# 16gpio_misc.net
KiCad netlist of a schematic drawn in Altium Designer
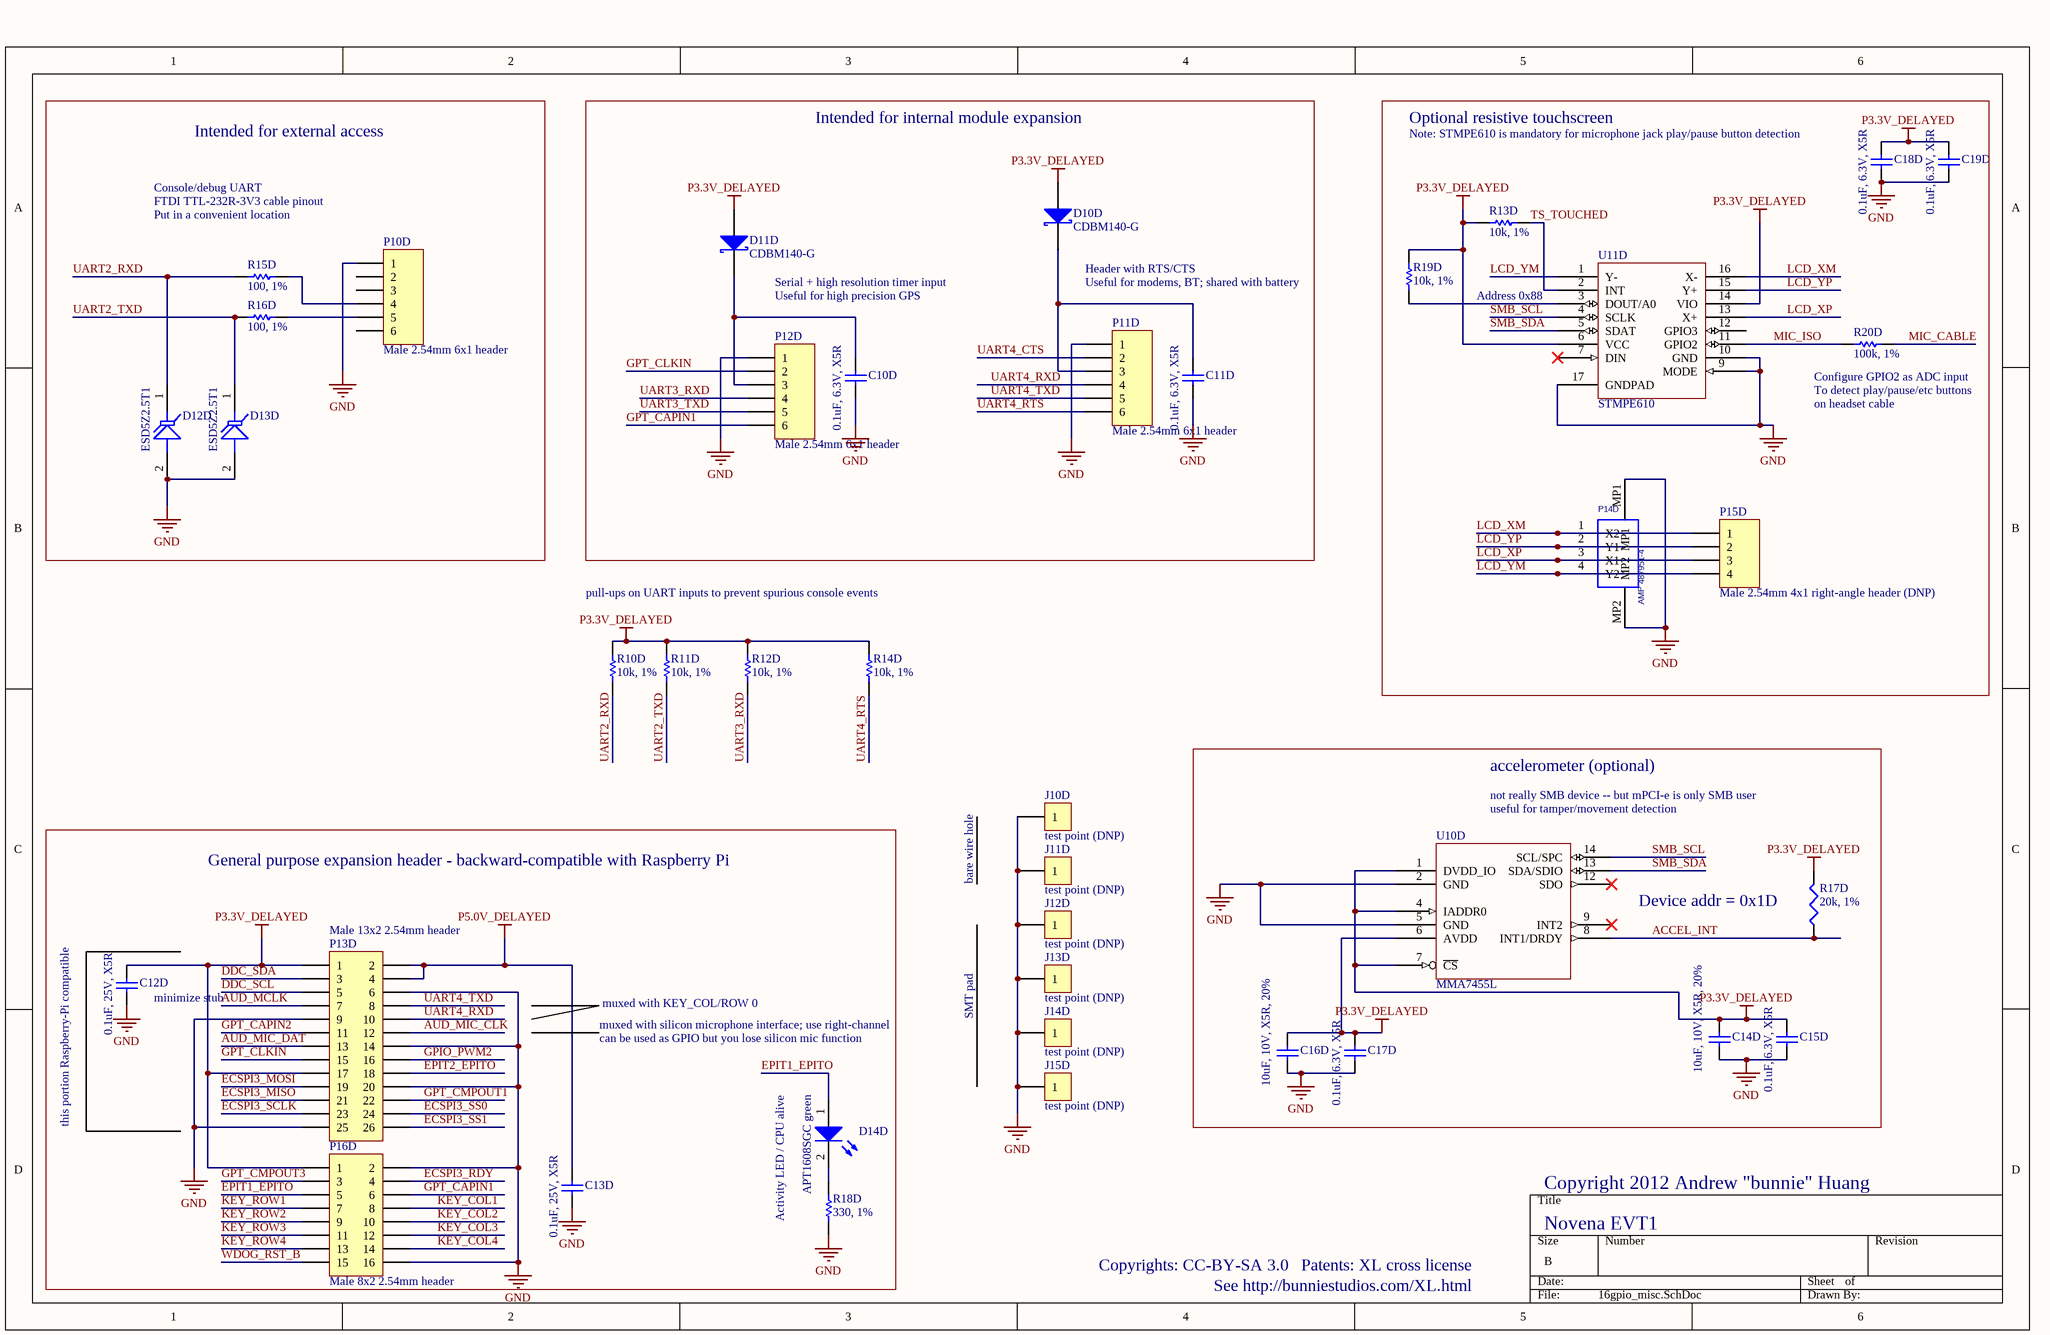
[diagram p0: 16gpio_misc.SchDoc]

(export (version "E")
  (design (tool "Eeschema 10.0.6"))
  (components
    (comp (ref "C10D")
      (value "0.1uF, 6.3V, X5R")
      (footprint "CAPC0603N_B")
      (description "Capacitor (Semiconductor SIM Model)")
      (fields (field (name "PUBLISHER") "Altium Limited"))
      (libsource (lib "Miscellaneous Devices") (part "Cap Semi"))
    )
    (comp (ref "C11D")
      (value "0.1uF, 6.3V, X5R")
      (footprint "CAPC0603N_B")
      (description "Capacitor (Semiconductor SIM Model)")
      (fields (field (name "PUBLISHER") "Altium Limited"))
      (libsource (lib "Miscellaneous Devices") (part "Cap Semi"))
    )
    (comp (ref "C12D")
      (value "0.1uF, 25V, X5R")
      (footprint "CAPC1005N")
      (description "Capacitor (Semiconductor SIM Model)")
      (fields (field (name "PUBLISHER") "Altium Limited"))
      (libsource (lib "Miscellaneous Devices") (part "Cap Semi"))
    )
    (comp (ref "C13D")
      (value "0.1uF, 25V, X5R")
      (footprint "CAPC1005N")
      (description "Capacitor (Semiconductor SIM Model)")
      (fields (field (name "PUBLISHER") "Altium Limited"))
      (libsource (lib "Miscellaneous Devices") (part "Cap Semi"))
    )
    (comp (ref "C14D")
      (value "10uF, 10V, X5R, 20%")
      (footprint "CAPC1608N")
      (description "Capacitor (Semiconductor SIM Model)")
      (fields (field (name "PUBLISHER") "Altium Limited"))
      (libsource (lib "Miscellaneous Devices") (part "Cap Semi"))
    )
    (comp (ref "C15D")
      (value "0.1uF, 6.3V, X5R")
      (footprint "CAPC0603N_B")
      (description "Capacitor (Semiconductor SIM Model)")
      (fields (field (name "PUBLISHER") "Altium Limited"))
      (libsource (lib "Miscellaneous Devices") (part "Cap Semi"))
    )
    (comp (ref "C16D")
      (value "10uF, 10V, X5R, 20%")
      (footprint "CAPC1608N")
      (description "Capacitor (Semiconductor SIM Model)")
      (fields (field (name "PUBLISHER") "Altium Limited"))
      (libsource (lib "Miscellaneous Devices") (part "Cap Semi"))
    )
    (comp (ref "C17D")
      (value "0.1uF, 6.3V, X5R")
      (footprint "CAPC0603N_B")
      (description "Capacitor (Semiconductor SIM Model)")
      (fields (field (name "PUBLISHER") "Altium Limited"))
      (libsource (lib "Miscellaneous Devices") (part "Cap Semi"))
    )
    (comp (ref "C18D")
      (value "0.1uF, 6.3V, X5R")
      (footprint "CAPC0603N_B")
      (description "Capacitor (Semiconductor SIM Model)")
      (fields (field (name "PUBLISHER") "Altium Limited"))
      (libsource (lib "Miscellaneous Devices") (part "Cap Semi"))
    )
    (comp (ref "C19D")
      (value "0.1uF, 6.3V, X5R")
      (footprint "CAPC0603N_B")
      (description "Capacitor (Semiconductor SIM Model)")
      (fields (field (name "PUBLISHER") "Altium Limited"))
      (libsource (lib "Miscellaneous Devices") (part "Cap Semi"))
    )
    (comp (ref "D10D")
      (value "CDBM140-G")
      (footprint "SOD123")
      (description "Schottky Diode")
      (fields (field (name "PUBLISHER") "Altium Limited"))
      (libsource (lib "Miscellaneous Devices") (part "D Schottky"))
    )
    (comp (ref "D11D")
      (value "CDBM140-G")
      (footprint "SOD123")
      (description "Schottky Diode")
      (fields (field (name "PUBLISHER") "Altium Limited"))
      (libsource (lib "Miscellaneous Devices") (part "D Schottky"))
    )
    (comp (ref "D12D")
      (value "ESD5Z2.5T1")
      (footprint "SOD-523")
      (description "On Semi 3.3V standoff TVS diode")
      (fields (field (name "PUBLISHER") "Altium Limited"))
      (libsource (lib "Miscellaneous Devices") (part "Tranzorb"))
    )
    (comp (ref "D13D")
      (value "ESD5Z2.5T1")
      (footprint "SOD-523")
      (description "On Semi 3.3V standoff TVS diode")
      (fields (field (name "PUBLISHER") "Altium Limited"))
      (libsource (lib "Miscellaneous Devices") (part "Tranzorb"))
    )
    (comp (ref "D14D")
      (value "APT1608SGC green")
      (footprint "CD1608-0603")
      (description "Typical RED, GREEN, YELLOW, AMBER GaAs LED")
      (fields (field (name "PUBLISHER") "Altium Limited"))
      (libsource (lib "Miscellaneous Devices") (part "LED2"))
    )
    (comp (ref "J10D")
      (value "test point (DNP)")
      (footprint "TP_HOLE")
      (description "Connector")
      (libsource (lib "*") (part "CON1"))
    )
    (comp (ref "J11D")
      (value "test point (DNP)")
      (footprint "TP_HOLE")
      (description "Connector")
      (libsource (lib "*") (part "CON1"))
    )
    (comp (ref "J12D")
      (value "test point (DNP)")
      (footprint "TP_SMT_38mil")
      (description "Connector")
      (libsource (lib "*") (part "CON1"))
    )
    (comp (ref "J13D")
      (value "test point (DNP)")
      (footprint "TP_SMT_38mil")
      (description "Connector")
      (libsource (lib "*") (part "CON1"))
    )
    (comp (ref "J14D")
      (value "test point (DNP)")
      (footprint "TP_SMT_38mil")
      (description "Connector")
      (libsource (lib "*") (part "CON1"))
    )
    (comp (ref "J15D")
      (value "test point (DNP)")
      (footprint "TP_SMT_38mil")
      (description "Connector")
      (libsource (lib "*") (part "CON1"))
    )
    (comp (ref "P10D")
      (value "Male 2.54mm 6x1 header")
      (footprint "HDR1X6")
      (description "Header, 6-Pin")
      (fields (field (name "PUBLISHER") "Altium Limited"))
      (libsource (lib "Miscellaneous Connectors") (part "Header 6"))
    )
    (comp (ref "P11D")
      (value "Male 2.54mm 6x1 header")
      (footprint "HDR1X6")
      (description "Header, 6-Pin")
      (fields (field (name "PUBLISHER") "Altium Limited"))
      (libsource (lib "Miscellaneous Connectors") (part "Header 6"))
    )
    (comp (ref "P12D")
      (value "Male 2.54mm 6x1 header")
      (footprint "HDR1X6")
      (description "Header, 6-Pin")
      (fields (field (name "PUBLISHER") "Altium Limited"))
      (libsource (lib "Miscellaneous Connectors") (part "Header 6"))
    )
    (comp (ref "P13D")
      (value "Male 13x2 2.54mm header")
      (footprint "HDR2X13")
      (description "Header, 13-Pin, Dual row")
      (fields (field (name "PUBLISHER") "Altium Limited"))
      (libsource (lib "Miscellaneous Connectors") (part "Header 13X2"))
    )
    (comp (ref "P14D") (value "AMP 487951-4") (libsource (lib "*") (part "TFT_TP_CON")))
    (comp (ref "P15D")
      (value "Male 2.54mm 4x1 right-angle header (DNP)")
      (footprint "HDR1X4H")
      (description "Header, 4-Pin, Right Angle")
      (fields (field (name "PUBLISHER") "Altium Limited"))
      (libsource (lib "Miscellaneous Connectors") (part "Header 4H"))
    )
    (comp (ref "P16D")
      (value "Male 8x2 2.54mm header")
      (footprint "HDR2X8")
      (description "Header, 8-Pin, Dual row")
      (fields (field (name "PUBLISHER") "Altium Limited"))
      (libsource (lib "Miscellaneous Connectors") (part "Header 8X2"))
    )
    (comp (ref "R10D")
      (value "10k, 1%")
      (footprint "RESC1005N")
      (description "Resistor")
      (fields (field (name "PUBLISHER") "Altium Limited"))
      (libsource (lib "Miscellaneous Devices") (part "Res1"))
    )
    (comp (ref "R11D")
      (value "10k, 1%")
      (footprint "RESC1005N")
      (description "Resistor")
      (fields (field (name "PUBLISHER") "Altium Limited"))
      (libsource (lib "Miscellaneous Devices") (part "Res1"))
    )
    (comp (ref "R12D")
      (value "10k, 1%")
      (footprint "RESC1005N")
      (description "Resistor")
      (fields (field (name "PUBLISHER") "Altium Limited"))
      (libsource (lib "Miscellaneous Devices") (part "Res1"))
    )
    (comp (ref "R13D")
      (value "10k, 1%")
      (footprint "RESC1005N")
      (description "Resistor")
      (fields (field (name "PUBLISHER") "Altium Limited"))
      (libsource (lib "Miscellaneous Devices") (part "Res1"))
    )
    (comp (ref "R14D")
      (value "10k, 1%")
      (footprint "RESC1005N")
      (description "Resistor")
      (fields (field (name "PUBLISHER") "Altium Limited"))
      (libsource (lib "Miscellaneous Devices") (part "Res1"))
    )
    (comp (ref "R15D")
      (value "100, 1%")
      (footprint "RESC1005N")
      (description "Resistor")
      (fields (field (name "PUBLISHER") "Altium Limited"))
      (libsource (lib "Miscellaneous Devices") (part "Res1"))
    )
    (comp (ref "R16D")
      (value "100, 1%")
      (footprint "RESC1005N")
      (description "Resistor")
      (fields (field (name "PUBLISHER") "Altium Limited"))
      (libsource (lib "Miscellaneous Devices") (part "Res1"))
    )
    (comp (ref "R17D")
      (value "20k, 1%")
      (footprint "RESC1005N")
      (description "Resistor")
      (fields (field (name "PUBLISHER") "Altium Limited"))
      (libsource (lib "Miscellaneous Devices") (part "Res3"))
    )
    (comp (ref "R18D")
      (value "330, 1%")
      (footprint "RESC1005N")
      (description "Resistor")
      (fields (field (name "PUBLISHER") "Altium Limited"))
      (libsource (lib "Miscellaneous Devices") (part "Res1"))
    )
    (comp (ref "R19D")
      (value "10k, 1%")
      (footprint "RESC1005N")
      (description "Resistor")
      (fields (field (name "PUBLISHER") "Altium Limited"))
      (libsource (lib "Miscellaneous Devices") (part "Res1"))
    )
    (comp (ref "R20D")
      (value "100k, 1%")
      (footprint "RESC1005N")
      (description "Resistor")
      (fields (field (name "PUBLISHER") "Altium Limited"))
      (libsource (lib "Miscellaneous Devices") (part "Res1"))
    )
    (comp (ref "U10D")
      (value "MMA7455L")
      (footprint "FREESCALE_LGA14_3mm_5mm")
      (description "3-axis accelerometer, 10 bit, selectable g-range")
      (libsource (lib "commonsch") (part "FREESCALE_MMA7455L"))
    )
    (comp (ref "U11D")
      (value "STMPE610")
      (footprint "QFN50P300X300-16V2N")
      (description "4-wire resistive touchscreen controller")
      (libsource (lib "commonsch") (part "STMPE610"))
    )
  )
  (nets
    (net (code "1") (name "/ACCEL_INT") (class "Default")
      (node (ref "R17D") (pin "1") (pinfunction "1_1") (pintype "passive"))
      (node (ref "U10D") (pin "8") (pinfunction "INT1/DRDY_8") (pintype "output"))
    )
    (net (code "2") (name "/AUD_MCLK") (class "Default")
      (node (ref "P13D") (pin "7") (pinfunction "7_7") (pintype "passive"))
    )
    (net (code "3") (name "/AUD_MIC_CLK") (class "Default")
      (node (ref "P13D") (pin "12") (pinfunction "12_12") (pintype "passive"))
    )
    (net (code "4") (name "/AUD_MIC_DAT") (class "Default")
      (node (ref "P13D") (pin "13") (pinfunction "13_13") (pintype "passive"))
    )
    (net (code "5") (name "/DDC_SCL") (class "Default")
      (node (ref "P13D") (pin "5") (pinfunction "5_5") (pintype "passive"))
    )
    (net (code "6") (name "/DDC_SDA") (class "Default")
      (node (ref "P13D") (pin "3") (pinfunction "3_3") (pintype "passive"))
    )
    (net (code "7") (name "/ECSPI3_MISO") (class "Default")
      (node (ref "P13D") (pin "21") (pinfunction "21_21") (pintype "passive"))
    )
    (net (code "8") (name "/ECSPI3_MOSI") (class "Default")
      (node (ref "P13D") (pin "19") (pinfunction "19_19") (pintype "passive"))
    )
    (net (code "9") (name "/ECSPI3_RDY") (class "Default")
      (node (ref "P16D") (pin "4") (pinfunction "4_4") (pintype "passive"))
    )
    (net (code "10") (name "/ECSPI3_SCLK") (class "Default")
      (node (ref "P13D") (pin "23") (pinfunction "23_23") (pintype "passive"))
    )
    (net (code "11") (name "/ECSPI3_SS0") (class "Default")
      (node (ref "P13D") (pin "24") (pinfunction "24_24") (pintype "passive"))
    )
    (net (code "12") (name "/ECSPI3_SS1") (class "Default")
      (node (ref "P13D") (pin "26") (pinfunction "26_26") (pintype "passive"))
    )
    (net (code "13") (name "/EPIT1_EPITO") (class "Default")
      (node (ref "D14D") (pin "1") (pinfunction "A_1") (pintype "passive"))
      (node (ref "P16D") (pin "5") (pinfunction "5_5") (pintype "passive"))
    )
    (net (code "14") (name "/EPIT2_EPITO") (class "Default")
      (node (ref "P13D") (pin "18") (pinfunction "18_18") (pintype "passive"))
    )
    (net (code "15") (name "/GPIO_PWM2") (class "Default")
      (node (ref "P13D") (pin "16") (pinfunction "16_16") (pintype "passive"))
    )
    (net (code "16") (name "/GPT_CAPIN1") (class "Default")
      (node (ref "P12D") (pin "6") (pinfunction "6_6") (pintype "passive"))
      (node (ref "P16D") (pin "6") (pinfunction "6_6") (pintype "passive"))
    )
    (net (code "17") (name "/GPT_CAPIN2") (class "Default")
      (node (ref "P13D") (pin "11") (pinfunction "11_11") (pintype "passive"))
    )
    (net (code "18") (name "/GPT_CLKIN") (class "Default")
      (node (ref "P12D") (pin "2") (pinfunction "2_2") (pintype "passive"))
      (node (ref "P13D") (pin "15") (pinfunction "15_15") (pintype "passive"))
    )
    (net (code "19") (name "/GPT_CMPOUT1") (class "Default")
      (node (ref "P13D") (pin "22") (pinfunction "22_22") (pintype "passive"))
    )
    (net (code "20") (name "/GPT_CMPOUT3") (class "Default")
      (node (ref "P16D") (pin "3") (pinfunction "3_3") (pintype "passive"))
    )
    (net (code "21") (name "/KEY_COL1") (class "Default")
      (node (ref "P16D") (pin "8") (pinfunction "8_8") (pintype "passive"))
    )
    (net (code "22") (name "/KEY_COL2") (class "Default")
      (node (ref "P16D") (pin "10") (pinfunction "10_10") (pintype "passive"))
    )
    (net (code "23") (name "/KEY_COL3") (class "Default")
      (node (ref "P16D") (pin "12") (pinfunction "12_12") (pintype "passive"))
    )
    (net (code "24") (name "/KEY_COL4") (class "Default")
      (node (ref "P16D") (pin "14") (pinfunction "14_14") (pintype "passive"))
    )
    (net (code "25") (name "/KEY_ROW1") (class "Default")
      (node (ref "P16D") (pin "7") (pinfunction "7_7") (pintype "passive"))
    )
    (net (code "26") (name "/KEY_ROW2") (class "Default")
      (node (ref "P16D") (pin "9") (pinfunction "9_9") (pintype "passive"))
    )
    (net (code "27") (name "/KEY_ROW3") (class "Default")
      (node (ref "P16D") (pin "11") (pinfunction "11_11") (pintype "passive"))
    )
    (net (code "28") (name "/KEY_ROW4") (class "Default")
      (node (ref "P16D") (pin "13") (pinfunction "13_13") (pintype "passive"))
    )
    (net (code "29") (name "/LCD_XM") (class "Default")
      (node (ref "P14D") (pin "1") (pinfunction "X2_1") (pintype "passive"))
      (node (ref "P15D") (pin "1") (pinfunction "1_1") (pintype "passive"))
      (node (ref "U11D") (pin "16") (pinfunction "X-_16") (pintype "passive"))
    )
    (net (code "30") (name "/LCD_XP") (class "Default")
      (node (ref "P14D") (pin "3") (pinfunction "X1_3") (pintype "passive"))
      (node (ref "P15D") (pin "3") (pinfunction "3_3") (pintype "passive"))
      (node (ref "U11D") (pin "13") (pinfunction "X+_13") (pintype "passive"))
    )
    (net (code "31") (name "/LCD_YM") (class "Default")
      (node (ref "P14D") (pin "4") (pinfunction "Y2_4") (pintype "passive"))
      (node (ref "P15D") (pin "4") (pinfunction "4_4") (pintype "passive"))
      (node (ref "U11D") (pin "1") (pinfunction "Y-_1") (pintype "passive"))
    )
    (net (code "32") (name "/LCD_YP") (class "Default")
      (node (ref "P14D") (pin "2") (pinfunction "Y1_2") (pintype "passive"))
      (node (ref "P15D") (pin "2") (pinfunction "2_2") (pintype "passive"))
      (node (ref "U11D") (pin "15") (pinfunction "Y+_15") (pintype "passive"))
    )
    (net (code "33") (name "/MIC_CABLE") (class "Default")
      (node (ref "R20D") (pin "2") (pinfunction "2_2") (pintype "passive"))
    )
    (net (code "34") (name "/MIC_ISO") (class "Default")
      (node (ref "R20D") (pin "1") (pinfunction "1_1") (pintype "passive"))
      (node (ref "U11D") (pin "11") (pinfunction "GPIO2_11") (pintype "bidirectional"))
    )
    (net (code "35") (name "/SMB_SCL") (class "Default")
      (node (ref "U10D") (pin "14") (pinfunction "SCL/SPC_14") (pintype "bidirectional"))
      (node (ref "U11D") (pin "4") (pinfunction "SCLK_4") (pintype "bidirectional"))
    )
    (net (code "36") (name "/SMB_SDA") (class "Default")
      (node (ref "U10D") (pin "13") (pinfunction "SDA/SDIO_13") (pintype "bidirectional"))
      (node (ref "U11D") (pin "5") (pinfunction "SDAT_5") (pintype "bidirectional"))
    )
    (net (code "37") (name "/TS_TOUCHED") (class "Default")
      (node (ref "R13D") (pin "1") (pinfunction "1_1") (pintype "passive"))
      (node (ref "U11D") (pin "2") (pinfunction "INT_2") (pintype "open_collector"))
    )
    (net (code "38") (name "/UART2_RXD") (class "Default")
      (node (ref "D12D") (pin "1") (pinfunction "K_1") (pintype "passive"))
      (node (ref "R10D") (pin "2") (pinfunction "2_2") (pintype "passive"))
      (node (ref "R15D") (pin "2") (pinfunction "2_2") (pintype "passive"))
    )
    (net (code "39") (name "/UART2_TXD") (class "Default")
      (node (ref "D13D") (pin "1") (pinfunction "K_1") (pintype "passive"))
      (node (ref "R11D") (pin "2") (pinfunction "2_2") (pintype "passive"))
      (node (ref "R16D") (pin "2") (pinfunction "2_2") (pintype "passive"))
    )
    (net (code "40") (name "/UART3_RXD") (class "Default")
      (node (ref "P12D") (pin "4") (pinfunction "4_4") (pintype "passive"))
      (node (ref "R12D") (pin "2") (pinfunction "2_2") (pintype "passive"))
    )
    (net (code "41") (name "/UART3_TXD") (class "Default")
      (node (ref "P12D") (pin "5") (pinfunction "5_5") (pintype "passive"))
    )
    (net (code "42") (name "/UART4_CTS") (class "Default")
      (node (ref "P11D") (pin "2") (pinfunction "2_2") (pintype "passive"))
    )
    (net (code "43") (name "/UART4_RTS") (class "Default")
      (node (ref "P11D") (pin "6") (pinfunction "6_6") (pintype "passive"))
      (node (ref "R14D") (pin "2") (pinfunction "2_2") (pintype "passive"))
    )
    (net (code "44") (name "/UART4_RXD") (class "Default")
      (node (ref "P11D") (pin "4") (pinfunction "4_4") (pintype "passive"))
      (node (ref "P13D") (pin "10") (pinfunction "10_10") (pintype "passive"))
    )
    (net (code "45") (name "/UART4_TXD") (class "Default")
      (node (ref "P11D") (pin "5") (pinfunction "5_5") (pintype "passive"))
      (node (ref "P13D") (pin "8") (pinfunction "8_8") (pintype "passive"))
    )
    (net (code "46") (name "/WDOG_RST_B") (class "Default")
      (node (ref "P16D") (pin "15") (pinfunction "15_15") (pintype "passive"))
    )
    (net (code "47") (name "GND") (class "Default")
      (node (ref "C10D") (pin "2") (pinfunction "2_2") (pintype "passive"))
      (node (ref "C11D") (pin "2") (pinfunction "2_2") (pintype "passive"))
      (node (ref "C12D") (pin "2") (pinfunction "2_2") (pintype "passive"))
      (node (ref "C13D") (pin "2") (pinfunction "2_2") (pintype "passive"))
      (node (ref "C14D") (pin "2") (pinfunction "2_2") (pintype "passive"))
      (node (ref "C15D") (pin "2") (pinfunction "2_2") (pintype "passive"))
      (node (ref "C16D") (pin "2") (pinfunction "2_2") (pintype "passive"))
      (node (ref "C17D") (pin "2") (pinfunction "2_2") (pintype "passive"))
      (node (ref "C18D") (pin "2") (pinfunction "2_2") (pintype "passive"))
      (node (ref "C19D") (pin "2") (pinfunction "2_2") (pintype "passive"))
      (node (ref "D12D") (pin "2") (pinfunction "A_2") (pintype "passive"))
      (node (ref "D13D") (pin "2") (pinfunction "A_2") (pintype "passive"))
      (node (ref "J10D") (pin "1") (pinfunction "1_1") (pintype "passive"))
      (node (ref "J11D") (pin "1") (pinfunction "1_1") (pintype "passive"))
      (node (ref "J12D") (pin "1") (pinfunction "1_1") (pintype "passive"))
      (node (ref "J13D") (pin "1") (pinfunction "1_1") (pintype "passive"))
      (node (ref "J14D") (pin "1") (pinfunction "1_1") (pintype "passive"))
      (node (ref "J15D") (pin "1") (pinfunction "1_1") (pintype "passive"))
      (node (ref "P10D") (pin "1") (pinfunction "1_1") (pintype "passive"))
      (node (ref "P11D") (pin "1") (pinfunction "1_1") (pintype "passive"))
      (node (ref "P12D") (pin "1") (pinfunction "1_1") (pintype "passive"))
      (node (ref "P13D") (pin "14") (pinfunction "14_14") (pintype "passive"))
      (node (ref "P13D") (pin "20") (pinfunction "20_20") (pintype "passive"))
      (node (ref "P13D") (pin "25") (pinfunction "25_25") (pintype "passive"))
      (node (ref "P13D") (pin "6") (pinfunction "6_6") (pintype "passive"))
      (node (ref "P13D") (pin "9") (pinfunction "9_9") (pintype "passive"))
      (node (ref "P14D") (pin "MP1") (pinfunction "MP1_MP1") (pintype "passive"))
      (node (ref "P14D") (pin "MP2") (pinfunction "MP2_MP2") (pintype "passive"))
      (node (ref "P16D") (pin "16") (pinfunction "16_16") (pintype "passive"))
      (node (ref "P16D") (pin "2") (pinfunction "2_2") (pintype "passive"))
      (node (ref "R18D") (pin "1") (pinfunction "1_1") (pintype "passive"))
      (node (ref "U10D") (pin "2") (pinfunction "GND_2") (pintype "power_in"))
      (node (ref "U10D") (pin "5") (pinfunction "GND_5") (pintype "power_in"))
      (node (ref "U11D") (pin "10") (pinfunction "GND_10") (pintype "power_in"))
      (node (ref "U11D") (pin "17") (pinfunction "GNDPAD_17") (pintype "power_in"))
      (node (ref "U11D") (pin "9") (pinfunction "MODE_9") (pintype "input"))
    )
    (net (code "48") (name "Net-(D10D-K)") (class "Default")
      (node (ref "C11D") (pin "1") (pinfunction "1_1") (pintype "passive"))
      (node (ref "D10D") (pin "2") (pinfunction "K_2") (pintype "passive"))
      (node (ref "P11D") (pin "3") (pinfunction "3_3") (pintype "passive"))
    )
    (net (code "49") (name "Net-(D11D-K)") (class "Default")
      (node (ref "C10D") (pin "1") (pinfunction "1_1") (pintype "passive"))
      (node (ref "D11D") (pin "2") (pinfunction "K_2") (pintype "passive"))
      (node (ref "P12D") (pin "3") (pinfunction "3_3") (pintype "passive"))
    )
    (net (code "50") (name "Net-(D14D-K)") (class "Default")
      (node (ref "D14D") (pin "2") (pinfunction "K_2") (pintype "passive"))
      (node (ref "R18D") (pin "2") (pinfunction "2_2") (pintype "passive"))
    )
    (net (code "51") (name "Net-(P10D-Pad4)") (class "Default")
      (node (ref "P10D") (pin "4") (pinfunction "4_4") (pintype "passive"))
      (node (ref "R15D") (pin "1") (pinfunction "1_1") (pintype "passive"))
    )
    (net (code "52") (name "Net-(P10D-Pad5)") (class "Default")
      (node (ref "P10D") (pin "5") (pinfunction "5_5") (pintype "passive"))
      (node (ref "R16D") (pin "1") (pinfunction "1_1") (pintype "passive"))
    )
    (net (code "53") (name "Net-(U11D-DOUT{slash}A0)") (class "Default")
      (node (ref "R19D") (pin "2") (pinfunction "2_2") (pintype "passive"))
      (node (ref "U11D") (pin "3") (pinfunction "DOUT/A0_3") (pintype "bidirectional"))
    )
    (net (code "54") (name "P3.3V_DELAYED") (class "Default")
      (node (ref "C12D") (pin "1") (pinfunction "1_1") (pintype "passive"))
      (node (ref "C14D") (pin "1") (pinfunction "1_1") (pintype "passive"))
      (node (ref "C15D") (pin "1") (pinfunction "1_1") (pintype "passive"))
      (node (ref "C16D") (pin "1") (pinfunction "1_1") (pintype "passive"))
      (node (ref "C17D") (pin "1") (pinfunction "1_1") (pintype "passive"))
      (node (ref "C18D") (pin "1") (pinfunction "1_1") (pintype "passive"))
      (node (ref "C19D") (pin "1") (pinfunction "1_1") (pintype "passive"))
      (node (ref "D10D") (pin "1") (pinfunction "A_1") (pintype "passive"))
      (node (ref "D11D") (pin "1") (pinfunction "A_1") (pintype "passive"))
      (node (ref "P13D") (pin "1") (pinfunction "1_1") (pintype "passive"))
      (node (ref "P13D") (pin "17") (pinfunction "17_17") (pintype "passive"))
      (node (ref "P16D") (pin "1") (pinfunction "1_1") (pintype "passive"))
      (node (ref "R10D") (pin "1") (pinfunction "1_1") (pintype "passive"))
      (node (ref "R11D") (pin "1") (pinfunction "1_1") (pintype "passive"))
      (node (ref "R12D") (pin "1") (pinfunction "1_1") (pintype "passive"))
      (node (ref "R13D") (pin "2") (pinfunction "2_2") (pintype "passive"))
      (node (ref "R14D") (pin "1") (pinfunction "1_1") (pintype "passive"))
      (node (ref "R17D") (pin "2") (pinfunction "2_2") (pintype "passive"))
      (node (ref "R19D") (pin "1") (pinfunction "1_1") (pintype "passive"))
      (node (ref "U10D") (pin "1") (pinfunction "DVDD_IO_1") (pintype "power_in"))
      (node (ref "U10D") (pin "4") (pinfunction "IADDR0_4") (pintype "input"))
      (node (ref "U10D") (pin "6") (pinfunction "AVDD_6") (pintype "power_in"))
      (node (ref "U10D") (pin "7") (pinfunction "~{CS}_7") (pintype "input"))
      (node (ref "U11D") (pin "14") (pinfunction "VIO_14") (pintype "power_in"))
      (node (ref "U11D") (pin "6") (pinfunction "VCC_6") (pintype "power_in"))
    )
    (net (code "55") (name "P5.0V_DELAYED") (class "Default")
      (node (ref "C13D") (pin "1") (pinfunction "1_1") (pintype "passive"))
      (node (ref "P13D") (pin "2") (pinfunction "2_2") (pintype "passive"))
      (node (ref "P13D") (pin "4") (pinfunction "4_4") (pintype "passive"))
    )
    (net (code "56") (name "unconnected-(P10D-Pad2)") (class "Default")
      (node (ref "P10D") (pin "2") (pinfunction "2_2") (pintype "passive"))
    )
    (net (code "57") (name "unconnected-(P10D-Pad3)") (class "Default")
      (node (ref "P10D") (pin "3") (pinfunction "3_3") (pintype "passive"))
    )
    (net (code "58") (name "unconnected-(P10D-Pad6)") (class "Default")
      (node (ref "P10D") (pin "6") (pinfunction "6_6") (pintype "passive"))
    )
    (net (code "59") (name "unconnected-(U10D-INT2-Pad9)") (class "Default")
      (node (ref "U10D") (pin "9") (pinfunction "INT2_9") (pintype "output+no_connect"))
    )
    (net (code "60") (name "unconnected-(U10D-SDO-Pad12)") (class "Default")
      (node (ref "U10D") (pin "12") (pinfunction "SDO_12") (pintype "output+no_connect"))
    )
    (net (code "61") (name "unconnected-(U11D-DIN-Pad7)") (class "Default")
      (node (ref "U11D") (pin "7") (pinfunction "DIN_7") (pintype "input+no_connect"))
    )
    (net (code "62") (name "unconnected-(U11D-GPIO3-Pad12)") (class "Default")
      (node (ref "U11D") (pin "12") (pinfunction "GPIO3_12") (pintype "bidirectional"))
    )
  )
)
